# LedDriver.net
KiCad netlist of a schematic drawn in Altium Designer
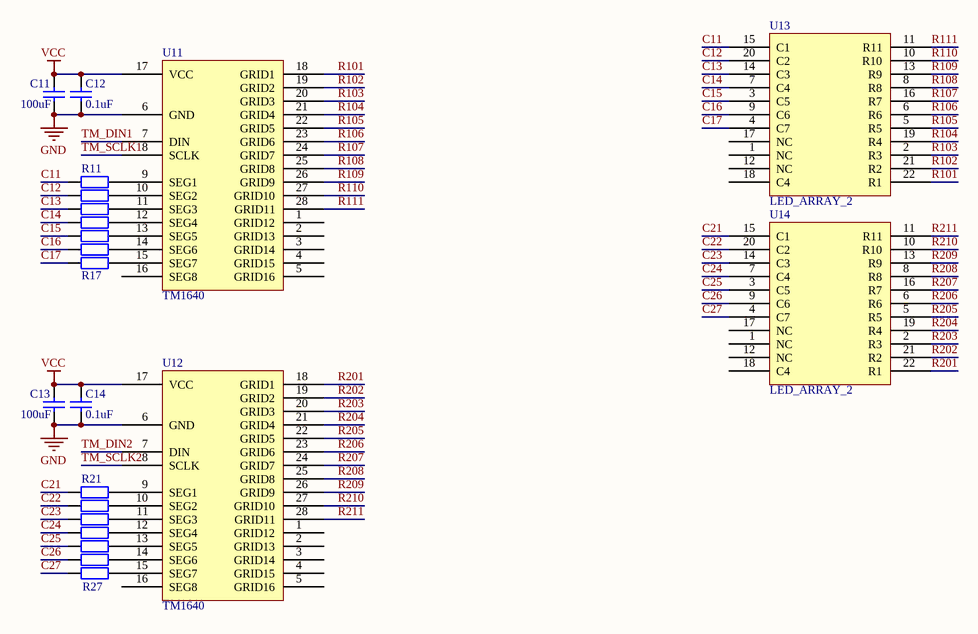
[diagram p0: LedDriver.SchDoc]

(export (version "E")
  (design (tool "Eeschema 10.0.6"))
  (components
    (comp (ref "C11")
      (value "100uF")
      (footprint "CAP-3528")
      (description "Capacitor")
      (fields (field (name "Comment") "Cap") (field (name "PUBLISHER") "Altium Limited"))
      (libsource (lib "Miscellaneous Devices") (part "Cap"))
    )
    (comp (ref "C12")
      (value "0.1uF")
      (footprint "C-0805")
      (description "Capacitor")
      (fields (field (name "Comment") "Cap") (field (name "PUBLISHER") "Altium Limited"))
      (libsource (lib "Miscellaneous Devices") (part "Cap"))
    )
    (comp (ref "C13")
      (value "100uF")
      (footprint "CAP-3528")
      (description "Capacitor")
      (fields (field (name "Comment") "Cap") (field (name "PUBLISHER") "Altium Limited"))
      (libsource (lib "Miscellaneous Devices") (part "Cap"))
    )
    (comp (ref "C14")
      (value "0.1uF")
      (footprint "C-0805")
      (description "Capacitor")
      (fields (field (name "Comment") "Cap") (field (name "PUBLISHER") "Altium Limited"))
      (libsource (lib "Miscellaneous Devices") (part "Cap"))
    )
    (comp (ref "R11")
      (value "Res2")
      (footprint "0805-1")
      (description "Resistor")
      (fields (field (name "PUBLISHER") "Altium Limited"))
      (libsource (lib "Miscellaneous Devices") (part "Res2"))
    )
    (comp (ref "R12")
      (value "Res2")
      (footprint "0805-1")
      (description "Resistor")
      (fields (field (name "PUBLISHER") "Altium Limited"))
      (libsource (lib "Miscellaneous Devices") (part "Res2"))
    )
    (comp (ref "R13")
      (value "Res2")
      (footprint "0805-1")
      (description "Resistor")
      (fields (field (name "PUBLISHER") "Altium Limited"))
      (libsource (lib "Miscellaneous Devices") (part "Res2"))
    )
    (comp (ref "R14")
      (value "Res2")
      (footprint "0805-1")
      (description "Resistor")
      (fields (field (name "PUBLISHER") "Altium Limited"))
      (libsource (lib "Miscellaneous Devices") (part "Res2"))
    )
    (comp (ref "R15")
      (value "Res2")
      (footprint "0805-1")
      (description "Resistor")
      (fields (field (name "PUBLISHER") "Altium Limited"))
      (libsource (lib "Miscellaneous Devices") (part "Res2"))
    )
    (comp (ref "R16")
      (value "Res2")
      (footprint "0805-1")
      (description "Resistor")
      (fields (field (name "PUBLISHER") "Altium Limited"))
      (libsource (lib "Miscellaneous Devices") (part "Res2"))
    )
    (comp (ref "R17")
      (value "Res2")
      (footprint "0805-1")
      (description "Resistor")
      (fields (field (name "PUBLISHER") "Altium Limited"))
      (libsource (lib "Miscellaneous Devices") (part "Res2"))
    )
    (comp (ref "R21")
      (value "Res2")
      (footprint "0805-1")
      (description "Resistor")
      (fields (field (name "PUBLISHER") "Altium Limited"))
      (libsource (lib "Miscellaneous Devices") (part "Res2"))
    )
    (comp (ref "R22")
      (value "Res2")
      (footprint "0805-1")
      (description "Resistor")
      (fields (field (name "PUBLISHER") "Altium Limited"))
      (libsource (lib "Miscellaneous Devices") (part "Res2"))
    )
    (comp (ref "R23")
      (value "Res2")
      (footprint "0805-1")
      (description "Resistor")
      (fields (field (name "PUBLISHER") "Altium Limited"))
      (libsource (lib "Miscellaneous Devices") (part "Res2"))
    )
    (comp (ref "R24")
      (value "Res2")
      (footprint "0805-1")
      (description "Resistor")
      (fields (field (name "PUBLISHER") "Altium Limited"))
      (libsource (lib "Miscellaneous Devices") (part "Res2"))
    )
    (comp (ref "R25")
      (value "Res2")
      (footprint "0805-1")
      (description "Resistor")
      (fields (field (name "PUBLISHER") "Altium Limited"))
      (libsource (lib "Miscellaneous Devices") (part "Res2"))
    )
    (comp (ref "R26")
      (value "Res2")
      (footprint "0805-1")
      (description "Resistor")
      (fields (field (name "PUBLISHER") "Altium Limited"))
      (libsource (lib "Miscellaneous Devices") (part "Res2"))
    )
    (comp (ref "R27")
      (value "Res2")
      (footprint "0805-1")
      (description "Resistor")
      (fields (field (name "PUBLISHER") "Altium Limited"))
      (libsource (lib "Miscellaneous Devices") (part "Res2"))
    )
    (comp (ref "U11")
      (value "TM1640")
      (footprint "SOIC28W")
      (description "8 段×16 位LED驱动芯片")
      (libsource (lib "Schlib1") (part "TM1640"))
    )
    (comp (ref "U12")
      (value "TM1640")
      (footprint "SOIC28W")
      (description "8 段×16 位LED驱动芯片")
      (libsource (lib "Schlib1") (part "TM1640"))
    )
    (comp (ref "U13")
      (value "LED_ARRAY_2")
      (footprint "DIP22_LEDARR")
      (libsource (lib "Schlib1") (part "LED_ARRAY_2"))
    )
    (comp (ref "U14")
      (value "LED_ARRAY_2")
      (footprint "DIP22_LEDARR")
      (libsource (lib "Schlib1") (part "LED_ARRAY_2"))
    )
  )
  (nets
    (net (code "1") (name "/C11") (class "Default")
      (node (ref "R11") (pin "1") (pinfunction "1_1") (pintype "passive"))
      (node (ref "U13") (pin "15") (pinfunction "C1_15") (pintype "passive"))
    )
    (net (code "2") (name "/C12") (class "Default")
      (node (ref "R12") (pin "1") (pinfunction "1_1") (pintype "passive"))
      (node (ref "U13") (pin "20") (pinfunction "C2_20") (pintype "passive"))
    )
    (net (code "3") (name "/C13") (class "Default")
      (node (ref "R13") (pin "1") (pinfunction "1_1") (pintype "passive"))
      (node (ref "U13") (pin "14") (pinfunction "C3_14") (pintype "passive"))
    )
    (net (code "4") (name "/C14") (class "Default")
      (node (ref "R14") (pin "1") (pinfunction "1_1") (pintype "passive"))
      (node (ref "U13") (pin "7") (pinfunction "C4_7") (pintype "passive"))
    )
    (net (code "5") (name "/C15") (class "Default")
      (node (ref "R15") (pin "1") (pinfunction "1_1") (pintype "passive"))
      (node (ref "U13") (pin "3") (pinfunction "C5_3") (pintype "passive"))
    )
    (net (code "6") (name "/C16") (class "Default")
      (node (ref "R16") (pin "1") (pinfunction "1_1") (pintype "passive"))
      (node (ref "U13") (pin "9") (pinfunction "C6_9") (pintype "passive"))
    )
    (net (code "7") (name "/C17") (class "Default")
      (node (ref "R17") (pin "1") (pinfunction "1_1") (pintype "passive"))
      (node (ref "U13") (pin "4") (pinfunction "C7_4") (pintype "passive"))
    )
    (net (code "8") (name "/C21") (class "Default")
      (node (ref "R21") (pin "1") (pinfunction "1_1") (pintype "passive"))
      (node (ref "U14") (pin "15") (pinfunction "C1_15") (pintype "passive"))
    )
    (net (code "9") (name "/C22") (class "Default")
      (node (ref "R22") (pin "1") (pinfunction "1_1") (pintype "passive"))
      (node (ref "U14") (pin "20") (pinfunction "C2_20") (pintype "passive"))
    )
    (net (code "10") (name "/C23") (class "Default")
      (node (ref "R23") (pin "1") (pinfunction "1_1") (pintype "passive"))
      (node (ref "U14") (pin "14") (pinfunction "C3_14") (pintype "passive"))
    )
    (net (code "11") (name "/C24") (class "Default")
      (node (ref "R24") (pin "1") (pinfunction "1_1") (pintype "passive"))
      (node (ref "U14") (pin "7") (pinfunction "C4_7") (pintype "passive"))
    )
    (net (code "12") (name "/C25") (class "Default")
      (node (ref "R25") (pin "1") (pinfunction "1_1") (pintype "passive"))
      (node (ref "U14") (pin "3") (pinfunction "C5_3") (pintype "passive"))
    )
    (net (code "13") (name "/C26") (class "Default")
      (node (ref "R26") (pin "1") (pinfunction "1_1") (pintype "passive"))
      (node (ref "U14") (pin "9") (pinfunction "C6_9") (pintype "passive"))
    )
    (net (code "14") (name "/C27") (class "Default")
      (node (ref "R27") (pin "1") (pinfunction "1_1") (pintype "passive"))
      (node (ref "U14") (pin "4") (pinfunction "C7_4") (pintype "passive"))
    )
    (net (code "15") (name "/R101") (class "Default")
      (node (ref "U11") (pin "18") (pinfunction "GRID1_18") (pintype "passive"))
      (node (ref "U13") (pin "22") (pinfunction "R1_22") (pintype "passive"))
    )
    (net (code "16") (name "/R102") (class "Default")
      (node (ref "U11") (pin "19") (pinfunction "GRID2_19") (pintype "passive"))
      (node (ref "U13") (pin "21") (pinfunction "R2_21") (pintype "passive"))
    )
    (net (code "17") (name "/R103") (class "Default")
      (node (ref "U11") (pin "20") (pinfunction "GRID3_20") (pintype "passive"))
      (node (ref "U13") (pin "2") (pinfunction "R3_2") (pintype "passive"))
    )
    (net (code "18") (name "/R104") (class "Default")
      (node (ref "U11") (pin "21") (pinfunction "GRID4_21") (pintype "passive"))
      (node (ref "U13") (pin "19") (pinfunction "R4_19") (pintype "passive"))
    )
    (net (code "19") (name "/R105") (class "Default")
      (node (ref "U11") (pin "22") (pinfunction "GRID5_22") (pintype "passive"))
      (node (ref "U13") (pin "5") (pinfunction "R5_5") (pintype "passive"))
    )
    (net (code "20") (name "/R106") (class "Default")
      (node (ref "U11") (pin "23") (pinfunction "GRID6_23") (pintype "passive"))
      (node (ref "U13") (pin "6") (pinfunction "R6_6") (pintype "passive"))
    )
    (net (code "21") (name "/R107") (class "Default")
      (node (ref "U11") (pin "24") (pinfunction "GRID7_24") (pintype "passive"))
      (node (ref "U13") (pin "16") (pinfunction "R7_16") (pintype "passive"))
    )
    (net (code "22") (name "/R108") (class "Default")
      (node (ref "U11") (pin "25") (pinfunction "GRID8_25") (pintype "passive"))
      (node (ref "U13") (pin "8") (pinfunction "R8_8") (pintype "passive"))
    )
    (net (code "23") (name "/R109") (class "Default")
      (node (ref "U11") (pin "26") (pinfunction "GRID9_26") (pintype "passive"))
      (node (ref "U13") (pin "13") (pinfunction "R9_13") (pintype "passive"))
    )
    (net (code "24") (name "/R110") (class "Default")
      (node (ref "U11") (pin "27") (pinfunction "GRID10_27") (pintype "passive"))
      (node (ref "U13") (pin "10") (pinfunction "R10_10") (pintype "passive"))
    )
    (net (code "25") (name "/R111") (class "Default")
      (node (ref "U11") (pin "28") (pinfunction "GRID11_28") (pintype "passive"))
      (node (ref "U13") (pin "11") (pinfunction "R11_11") (pintype "passive"))
    )
    (net (code "26") (name "/R201") (class "Default")
      (node (ref "U12") (pin "18") (pinfunction "GRID1_18") (pintype "passive"))
      (node (ref "U14") (pin "22") (pinfunction "R1_22") (pintype "passive"))
    )
    (net (code "27") (name "/R202") (class "Default")
      (node (ref "U12") (pin "19") (pinfunction "GRID2_19") (pintype "passive"))
      (node (ref "U14") (pin "21") (pinfunction "R2_21") (pintype "passive"))
    )
    (net (code "28") (name "/R203") (class "Default")
      (node (ref "U12") (pin "20") (pinfunction "GRID3_20") (pintype "passive"))
      (node (ref "U14") (pin "2") (pinfunction "R3_2") (pintype "passive"))
    )
    (net (code "29") (name "/R204") (class "Default")
      (node (ref "U12") (pin "21") (pinfunction "GRID4_21") (pintype "passive"))
      (node (ref "U14") (pin "19") (pinfunction "R4_19") (pintype "passive"))
    )
    (net (code "30") (name "/R205") (class "Default")
      (node (ref "U12") (pin "22") (pinfunction "GRID5_22") (pintype "passive"))
      (node (ref "U14") (pin "5") (pinfunction "R5_5") (pintype "passive"))
    )
    (net (code "31") (name "/R206") (class "Default")
      (node (ref "U12") (pin "23") (pinfunction "GRID6_23") (pintype "passive"))
      (node (ref "U14") (pin "6") (pinfunction "R6_6") (pintype "passive"))
    )
    (net (code "32") (name "/R207") (class "Default")
      (node (ref "U12") (pin "24") (pinfunction "GRID7_24") (pintype "passive"))
      (node (ref "U14") (pin "16") (pinfunction "R7_16") (pintype "passive"))
    )
    (net (code "33") (name "/R208") (class "Default")
      (node (ref "U12") (pin "25") (pinfunction "GRID8_25") (pintype "passive"))
      (node (ref "U14") (pin "8") (pinfunction "R8_8") (pintype "passive"))
    )
    (net (code "34") (name "/R209") (class "Default")
      (node (ref "U12") (pin "26") (pinfunction "GRID9_26") (pintype "passive"))
      (node (ref "U14") (pin "13") (pinfunction "R9_13") (pintype "passive"))
    )
    (net (code "35") (name "/R210") (class "Default")
      (node (ref "U12") (pin "27") (pinfunction "GRID10_27") (pintype "passive"))
      (node (ref "U14") (pin "10") (pinfunction "R10_10") (pintype "passive"))
    )
    (net (code "36") (name "/R211") (class "Default")
      (node (ref "U12") (pin "28") (pinfunction "GRID11_28") (pintype "passive"))
      (node (ref "U14") (pin "11") (pinfunction "R11_11") (pintype "passive"))
    )
    (net (code "37") (name "/TM_DIN1") (class "Default")
      (node (ref "U11") (pin "7") (pinfunction "DIN_7") (pintype "passive"))
    )
    (net (code "38") (name "/TM_DIN2") (class "Default")
      (node (ref "U12") (pin "7") (pinfunction "DIN_7") (pintype "passive"))
    )
    (net (code "39") (name "/TM_SCLK1") (class "Default")
      (node (ref "U11") (pin "8") (pinfunction "SCLK_8") (pintype "passive"))
    )
    (net (code "40") (name "/TM_SCLK2") (class "Default")
      (node (ref "U12") (pin "8") (pinfunction "SCLK_8") (pintype "passive"))
    )
    (net (code "41") (name "GND") (class "Default")
      (node (ref "C11") (pin "1") (pinfunction "1_1") (pintype "passive"))
      (node (ref "C12") (pin "1") (pinfunction "1_1") (pintype "passive"))
      (node (ref "C13") (pin "1") (pinfunction "1_1") (pintype "passive"))
      (node (ref "C14") (pin "1") (pinfunction "1_1") (pintype "passive"))
      (node (ref "U11") (pin "6") (pinfunction "GND_6") (pintype "passive"))
      (node (ref "U12") (pin "6") (pinfunction "GND_6") (pintype "passive"))
    )
    (net (code "42") (name "Net-(U11-SEG1)") (class "Default")
      (node (ref "R11") (pin "2") (pinfunction "2_2") (pintype "passive"))
      (node (ref "U11") (pin "9") (pinfunction "SEG1_9") (pintype "passive"))
    )
    (net (code "43") (name "Net-(U11-SEG2)") (class "Default")
      (node (ref "R12") (pin "2") (pinfunction "2_2") (pintype "passive"))
      (node (ref "U11") (pin "10") (pinfunction "SEG2_10") (pintype "passive"))
    )
    (net (code "44") (name "Net-(U11-SEG3)") (class "Default")
      (node (ref "R13") (pin "2") (pinfunction "2_2") (pintype "passive"))
      (node (ref "U11") (pin "11") (pinfunction "SEG3_11") (pintype "passive"))
    )
    (net (code "45") (name "Net-(U11-SEG4)") (class "Default")
      (node (ref "R14") (pin "2") (pinfunction "2_2") (pintype "passive"))
      (node (ref "U11") (pin "12") (pinfunction "SEG4_12") (pintype "passive"))
    )
    (net (code "46") (name "Net-(U11-SEG5)") (class "Default")
      (node (ref "R15") (pin "2") (pinfunction "2_2") (pintype "passive"))
      (node (ref "U11") (pin "13") (pinfunction "SEG5_13") (pintype "passive"))
    )
    (net (code "47") (name "Net-(U11-SEG6)") (class "Default")
      (node (ref "R16") (pin "2") (pinfunction "2_2") (pintype "passive"))
      (node (ref "U11") (pin "14") (pinfunction "SEG6_14") (pintype "passive"))
    )
    (net (code "48") (name "Net-(U11-SEG7)") (class "Default")
      (node (ref "R17") (pin "2") (pinfunction "2_2") (pintype "passive"))
      (node (ref "U11") (pin "15") (pinfunction "SEG7_15") (pintype "passive"))
    )
    (net (code "49") (name "Net-(U12-SEG1)") (class "Default")
      (node (ref "R21") (pin "2") (pinfunction "2_2") (pintype "passive"))
      (node (ref "U12") (pin "9") (pinfunction "SEG1_9") (pintype "passive"))
    )
    (net (code "50") (name "Net-(U12-SEG2)") (class "Default")
      (node (ref "R22") (pin "2") (pinfunction "2_2") (pintype "passive"))
      (node (ref "U12") (pin "10") (pinfunction "SEG2_10") (pintype "passive"))
    )
    (net (code "51") (name "Net-(U12-SEG3)") (class "Default")
      (node (ref "R23") (pin "2") (pinfunction "2_2") (pintype "passive"))
      (node (ref "U12") (pin "11") (pinfunction "SEG3_11") (pintype "passive"))
    )
    (net (code "52") (name "Net-(U12-SEG4)") (class "Default")
      (node (ref "R24") (pin "2") (pinfunction "2_2") (pintype "passive"))
      (node (ref "U12") (pin "12") (pinfunction "SEG4_12") (pintype "passive"))
    )
    (net (code "53") (name "Net-(U12-SEG5)") (class "Default")
      (node (ref "R25") (pin "2") (pinfunction "2_2") (pintype "passive"))
      (node (ref "U12") (pin "13") (pinfunction "SEG5_13") (pintype "passive"))
    )
    (net (code "54") (name "Net-(U12-SEG6)") (class "Default")
      (node (ref "R26") (pin "2") (pinfunction "2_2") (pintype "passive"))
      (node (ref "U12") (pin "14") (pinfunction "SEG6_14") (pintype "passive"))
    )
    (net (code "55") (name "Net-(U12-SEG7)") (class "Default")
      (node (ref "R27") (pin "2") (pinfunction "2_2") (pintype "passive"))
      (node (ref "U12") (pin "15") (pinfunction "SEG7_15") (pintype "passive"))
    )
    (net (code "56") (name "VCC") (class "Default")
      (node (ref "C11") (pin "2") (pinfunction "2_2") (pintype "passive"))
      (node (ref "C12") (pin "2") (pinfunction "2_2") (pintype "passive"))
      (node (ref "C13") (pin "2") (pinfunction "2_2") (pintype "passive"))
      (node (ref "C14") (pin "2") (pinfunction "2_2") (pintype "passive"))
      (node (ref "U11") (pin "17") (pinfunction "VCC_17") (pintype "passive"))
      (node (ref "U12") (pin "17") (pinfunction "VCC_17") (pintype "passive"))
    )
    (net (code "57") (name "unconnected-(U11-GRID12-Pad1)") (class "Default")
      (node (ref "U11") (pin "1") (pinfunction "GRID12_1") (pintype "passive"))
    )
    (net (code "58") (name "unconnected-(U11-GRID13-Pad2)") (class "Default")
      (node (ref "U11") (pin "2") (pinfunction "GRID13_2") (pintype "passive"))
    )
    (net (code "59") (name "unconnected-(U11-GRID14-Pad3)") (class "Default")
      (node (ref "U11") (pin "3") (pinfunction "GRID14_3") (pintype "passive"))
    )
    (net (code "60") (name "unconnected-(U11-GRID15-Pad4)") (class "Default")
      (node (ref "U11") (pin "4") (pinfunction "GRID15_4") (pintype "passive"))
    )
    (net (code "61") (name "unconnected-(U11-GRID16-Pad5)") (class "Default")
      (node (ref "U11") (pin "5") (pinfunction "GRID16_5") (pintype "passive"))
    )
    (net (code "62") (name "unconnected-(U11-SEG8-Pad16)") (class "Default")
      (node (ref "U11") (pin "16") (pinfunction "SEG8_16") (pintype "passive"))
    )
    (net (code "63") (name "unconnected-(U12-GRID12-Pad1)") (class "Default")
      (node (ref "U12") (pin "1") (pinfunction "GRID12_1") (pintype "passive"))
    )
    (net (code "64") (name "unconnected-(U12-GRID13-Pad2)") (class "Default")
      (node (ref "U12") (pin "2") (pinfunction "GRID13_2") (pintype "passive"))
    )
    (net (code "65") (name "unconnected-(U12-GRID14-Pad3)") (class "Default")
      (node (ref "U12") (pin "3") (pinfunction "GRID14_3") (pintype "passive"))
    )
    (net (code "66") (name "unconnected-(U12-GRID15-Pad4)") (class "Default")
      (node (ref "U12") (pin "4") (pinfunction "GRID15_4") (pintype "passive"))
    )
    (net (code "67") (name "unconnected-(U12-GRID16-Pad5)") (class "Default")
      (node (ref "U12") (pin "5") (pinfunction "GRID16_5") (pintype "passive"))
    )
    (net (code "68") (name "unconnected-(U12-SEG8-Pad16)") (class "Default")
      (node (ref "U12") (pin "16") (pinfunction "SEG8_16") (pintype "passive"))
    )
    (net (code "69") (name "unconnected-(U13-C4-Pad18)") (class "Default")
      (node (ref "U13") (pin "18") (pinfunction "C4_18") (pintype "passive"))
    )
    (net (code "70") (name "unconnected-(U13-NC-Pad1)") (class "Default")
      (node (ref "U13") (pin "1") (pinfunction "NC_1") (pintype "passive"))
    )
    (net (code "71") (name "unconnected-(U13-NC-Pad12)") (class "Default")
      (node (ref "U13") (pin "12") (pinfunction "NC_12") (pintype "passive"))
    )
    (net (code "72") (name "unconnected-(U13-NC-Pad17)") (class "Default")
      (node (ref "U13") (pin "17") (pinfunction "NC_17") (pintype "passive"))
    )
    (net (code "73") (name "unconnected-(U14-C4-Pad18)") (class "Default")
      (node (ref "U14") (pin "18") (pinfunction "C4_18") (pintype "passive"))
    )
    (net (code "74") (name "unconnected-(U14-NC-Pad1)") (class "Default")
      (node (ref "U14") (pin "1") (pinfunction "NC_1") (pintype "passive"))
    )
    (net (code "75") (name "unconnected-(U14-NC-Pad12)") (class "Default")
      (node (ref "U14") (pin "12") (pinfunction "NC_12") (pintype "passive"))
    )
    (net (code "76") (name "unconnected-(U14-NC-Pad17)") (class "Default")
      (node (ref "U14") (pin "17") (pinfunction "NC_17") (pintype "passive"))
    )
  )
)
